# TOP_Sheet.net
KiCad netlist of a schematic drawn in Altium Designer
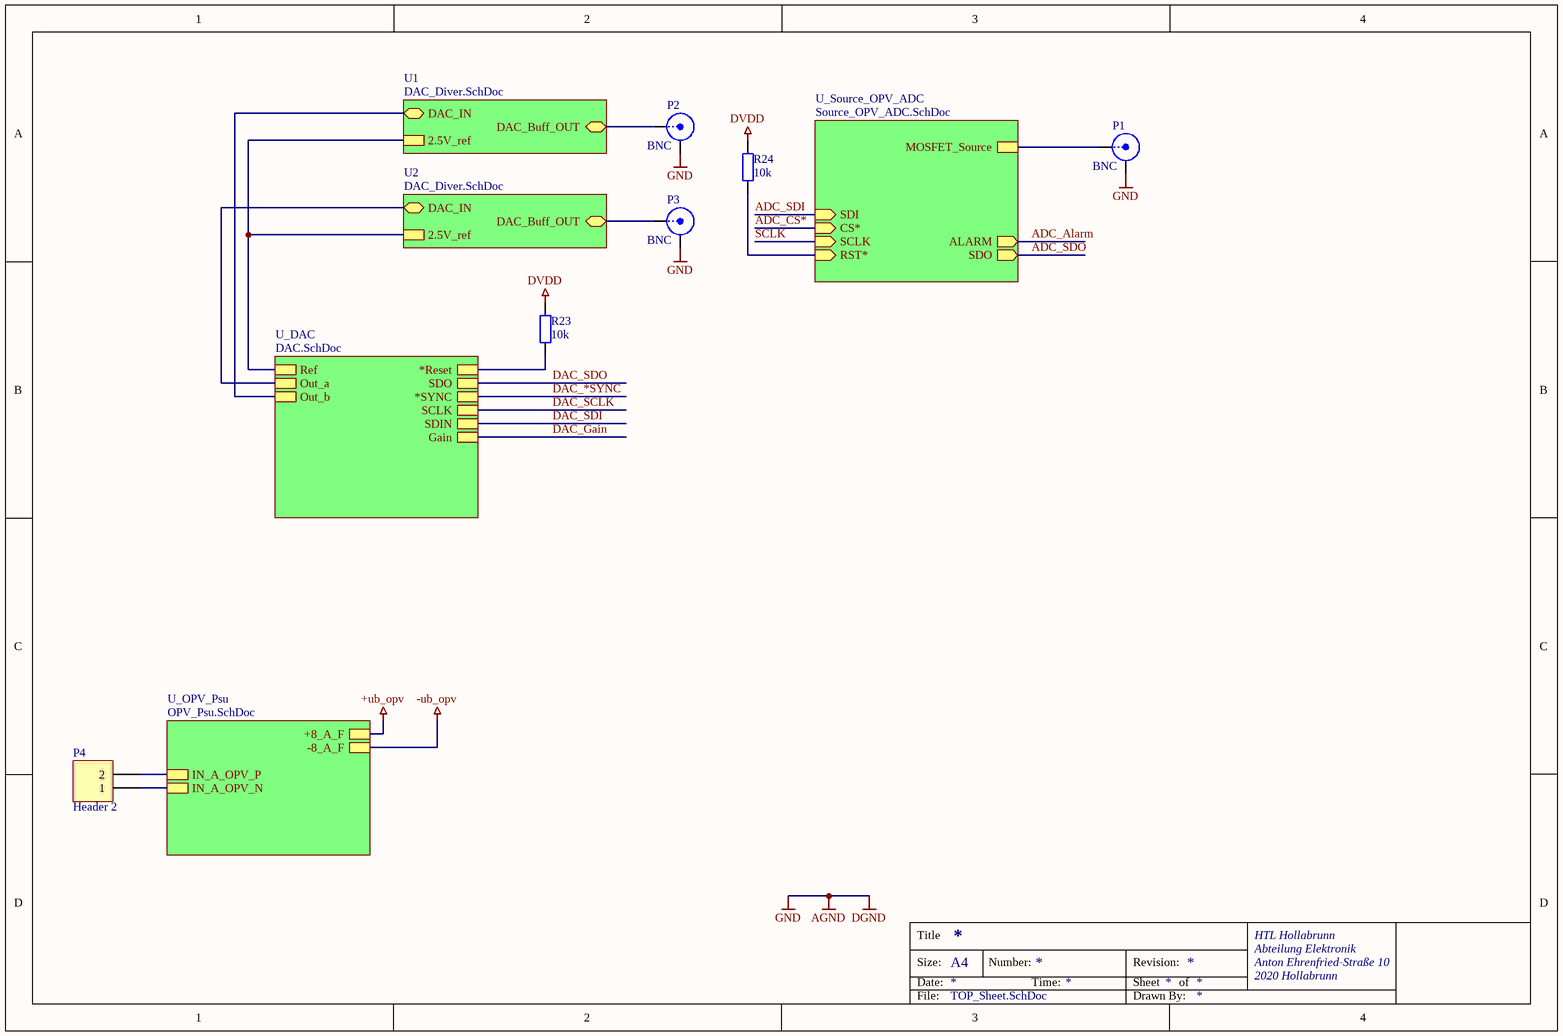
[diagram p0: TOP_Sheet.SchDoc]

(export (version "E")
  (design (tool "Eeschema 10.0.6"))
  (components
    (comp (ref "P1")
      (value "BNC")
      (footprint "BNC_RA CON")
      (description "BNC Elbow Connector")
      (fields (field (name "PUBLISHER") "Altium Limited"))
      (libsource (lib "Miscellaneous Connectors") (part "BNC"))
    )
    (comp (ref "P2")
      (value "BNC")
      (footprint "BNC_RA CON")
      (description "BNC Elbow Connector")
      (fields (field (name "PUBLISHER") "Altium Limited"))
      (libsource (lib "Miscellaneous Connectors") (part "BNC"))
    )
    (comp (ref "P3")
      (value "BNC")
      (footprint "BNC_RA CON")
      (description "BNC Elbow Connector")
      (fields (field (name "PUBLISHER") "Altium Limited"))
      (libsource (lib "Miscellaneous Connectors") (part "BNC"))
    )
    (comp (ref "P4")
      (value "Header 2")
      (footprint "HDR1X2")
      (description "Header, 2-Pin")
      (fields (field (name "PUBLISHER") "Altium Limited"))
      (libsource (lib "Miscellaneous Connectors") (part "Header 2"))
    )
    (comp (ref "R23")
      (value "10k")
      (footprint "C1206-KUE")
      (description "Resistor SMD")
      (fields (field (name "MANUFACTURER") "AVX") (field (name "PUBLISHER") "Altium Limited"))
      (libsource (lib "ExtrapartsKUE_V01") (part "ResistorSMD"))
    )
    (comp (ref "R24")
      (value "10k")
      (footprint "C1206-KUE")
      (description "Resistor SMD")
      (fields (field (name "MANUFACTURER") "AVX") (field (name "PUBLISHER") "Altium Limited"))
      (libsource (lib "ExtrapartsKUE_V01") (part "ResistorSMD"))
    )
  )
  (nets
    (net (code "3") (name "/*Reset") (class "Default")
      (node (ref "R23") (pin "2") (pinfunction "2_2") (pintype "passive"))
    )
    (net (code "10") (name "/DAC_Buff_OUT") (class "Default")
      (node (ref "P3") (pin "1") (pinfunction "X_1") (pintype "passive"))
    )
    (net (code "11") (name "/DAC_Buff_OUT_1") (class "Default")
      (node (ref "P2") (pin "1") (pinfunction "X_1") (pintype "passive"))
    )
    (net (code "18") (name "/IN_A_OPV_N") (class "Default")
      (node (ref "P4") (pin "1") (pinfunction "1_1") (pintype "passive"))
    )
    (net (code "19") (name "/IN_A_OPV_P") (class "Default")
      (node (ref "P4") (pin "2") (pinfunction "2_2") (pintype "passive"))
    )
    (net (code "20") (name "/MOSFET_Source") (class "Default")
      (node (ref "P1") (pin "1") (pinfunction "X_1") (pintype "passive"))
    )
    (net (code "21") (name "/RST*") (class "Default")
      (node (ref "R24") (pin "2") (pinfunction "2_2") (pintype "passive"))
    )
    (net (code "23") (name "AGND") (class "Default")
      (node (ref "P1") (pin "2") (pinfunction "Y_2") (pintype "passive"))
      (node (ref "P2") (pin "2") (pinfunction "Y_2") (pintype "passive"))
      (node (ref "P3") (pin "2") (pinfunction "Y_2") (pintype "passive"))
    )
    (net (code "24") (name "DVDD") (class "Default")
      (node (ref "R23") (pin "1") (pinfunction "1_1") (pintype "passive"))
      (node (ref "R24") (pin "1") (pinfunction "1_1") (pintype "passive"))
    )
  )
)
